# EMG_Interface.net
KiCad netlist of a schematic drawn in Altium Designer
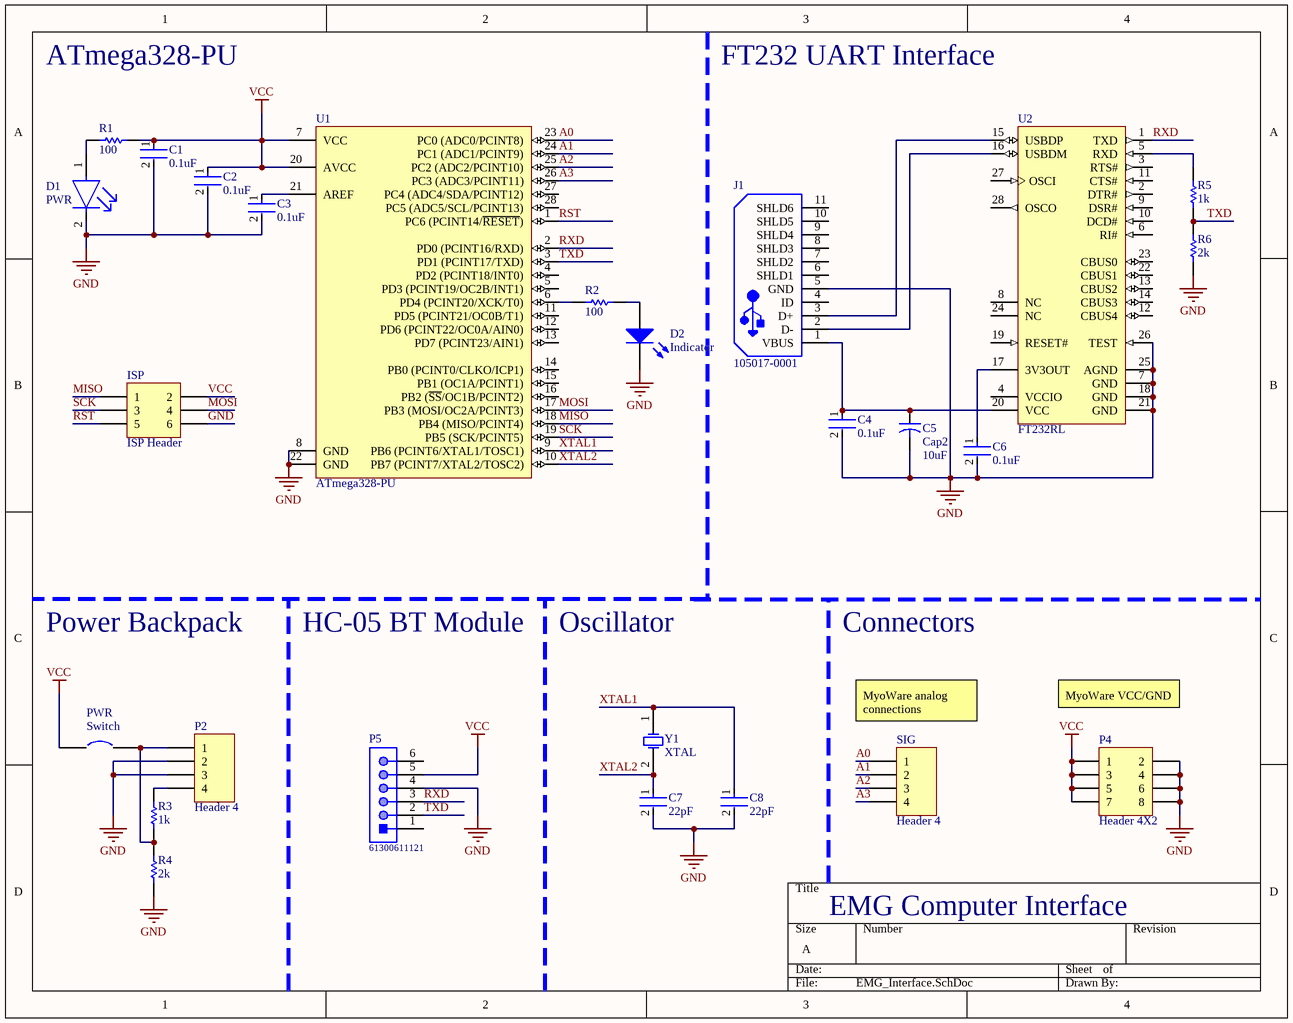
[diagram p0: EMG_Interface.SchDoc]

(export (version "E")
  (design (tool "Eeschema 10.0.6"))
  (components
    (comp (ref "C1")
      (value "0.1uF")
      (footprint "FP-1206-L_3_2_0_2-W_1_6_0-IPC_C")
      (description "General Purpose Ceramic Capacitor, 1206, 100nF, 5%, X7R, 15%, 100V")
      (fields (field (name "TOLERANCE") "5%") (field (name "VOLTAGE") "100V"))
      (libsource (lib "Altium Content Vault") (part "b4654b650e69147ec39a6b967a45e02"))
    )
    (comp (ref "C2")
      (value "0.1uF")
      (footprint "FP-1206-L_3_2_0_2-W_1_6_0-IPC_C")
      (description "General Purpose Ceramic Capacitor, 1206, 100nF, 5%, X7R, 15%, 100V")
      (fields (field (name "TOLERANCE") "5%") (field (name "VOLTAGE") "100V"))
      (libsource (lib "Altium Content Vault") (part "b4654b650e69147ec39a6b967a45e02"))
    )
    (comp (ref "C3")
      (value "0.1uF")
      (footprint "FP-1206-L_3_2_0_2-W_1_6_0-IPC_C")
      (description "General Purpose Ceramic Capacitor, 1206, 100nF, 5%, X7R, 15%, 100V")
      (fields (field (name "TOLERANCE") "5%") (field (name "VOLTAGE") "100V"))
      (libsource (lib "Altium Content Vault") (part "b4654b650e69147ec39a6b967a45e02"))
    )
    (comp (ref "C4")
      (value "0.1uF")
      (footprint "FP-1206-L_3_2_0_2-W_1_6_0-IPC_C")
      (description "General Purpose Ceramic Capacitor, 1206, 100nF, 5%, X7R, 15%, 100V")
      (fields (field (name "TOLERANCE") "5%") (field (name "VOLTAGE") "100V"))
      (libsource (lib "Altium Content Vault") (part "b4654b650e69147ec39a6b967a45e02"))
    )
    (comp (ref "C5")
      (value "Cap2")
      (footprint "CAPR5-4X5")
      (description "Capacitor")
      (fields (field (name "ALTIUM_VALUE") "10uF") (field (name "PUBLISHER") "Altium Limited"))
      (libsource (lib "Miscellaneous Devices") (part "Cap2"))
    )
    (comp (ref "C6")
      (value "0.1uF")
      (footprint "FP-1206-L_3_2_0_2-W_1_6_0-IPC_C")
      (description "General Purpose Ceramic Capacitor, 1206, 100nF, 5%, X7R, 15%, 100V")
      (fields (field (name "TOLERANCE") "5%") (field (name "VOLTAGE") "100V"))
      (libsource (lib "Altium Content Vault") (part "b4654b650e69147ec39a6b967a45e02"))
    )
    (comp (ref "C7")
      (value "22pF")
      (footprint "FP-C1206C-EB-MFG")
      (description "1206 22pF Ceramic Multilayer Capacitor; 50VDC; 125degC; C0G Dielec; +/-5% SMD")
      (fields
        (field (name "OCTOPART") "https://octopart.com/c1206c220j5gactu-kemet-131912")
        (field (name "TOLERANCE") "0.05")
      )
      (libsource (lib "Altium Content Vault") (part "b4654b650e69147ec39a6b967a45e02"))
    )
    (comp (ref "C8")
      (value "22pF")
      (footprint "FP-C1206C-EB-MFG")
      (description "1206 22pF Ceramic Multilayer Capacitor; 50VDC; 125degC; C0G Dielec; +/-5% SMD")
      (fields
        (field (name "OCTOPART") "https://octopart.com/c1206c220j5gactu-kemet-131912")
        (field (name "TOLERANCE") "0.05")
      )
      (libsource (lib "Altium Content Vault") (part "b4654b650e69147ec39a6b967a45e02"))
    )
    (comp (ref "D1")
      (value "PWR")
      (footprint "FP-SML-LX1206GC-TR-MFG")
      (description "LED GREEN CLEAR 1206 SMD")
      (libsource (lib "Altium Content Vault") (part "ab1c01a81903e929fc6c44469aada92"))
    )
    (comp (ref "D2")
      (value "Indicator")
      (footprint "1206_A")
      (description "SMD mono-color Chip LED, WL-SMCW, Super Red")
      (fields (field (name "MANUFACTURER") "Wuerth Elektronik") (field (name "PARTNUMBER") "150120SS75000"))
      (libsource (lib "Altium Content Vault") (part "WE-LED_K1A2-2"))
    )
    (comp (ref "ISP")
      (value "ISP Header")
      (footprint "HDR2X3")
      (description "Header, 3-Pin, Dual row")
      (fields (field (name "PUBLISHER") "Altium Limited"))
      (libsource (lib "Miscellaneous Connectors") (part "Header 3X2"))
    )
    (comp (ref "J1")
      (value "105017-0001")
      (footprint "USB-MICRO-B_V")
      (fields (field (name "MANUFACTURER") "Molex"))
      (libsource (lib "Altium Content Vault") (part "USB-5-6SHLD"))
    )
    (comp (ref "P2")
      (value "Header 4")
      (footprint "HDR1X4")
      (description "Header, 4-Pin")
      (fields (field (name "PUBLISHER") "Altium Limited"))
      (libsource (lib "Miscellaneous Connectors") (part "Header 4"))
    )
    (comp (ref "P4")
      (value "Header 4X2")
      (footprint "HDR2X4")
      (description "Header, 4-Pin, Dual row")
      (fields (field (name "PUBLISHER") "Altium Limited"))
      (libsource (lib "Miscellaneous Connectors") (part "Header 4X2"))
    )
    (comp (ref "P5")
      (value "61300611121")
      (footprint "61300611121")
      (description "THT Vertical Pin Header WR-PHD, Pitch 2.54 mm, Single Row, 6 pins")
      (fields (field (name "MANUFACTURER") "Wurth Elektronik") (field (name "PUBLISHER") "WurthElektronik"))
      (libsource (lib "Altium Content Vault") (part "WE-CN-1P-M-R6"))
    )
    (comp (ref "PWR")
      (value "Switch")
      (footprint "SPST-2")
      (description "Circuit Breaker")
      (fields (field (name "PUBLISHER") "Altium Limited"))
      (libsource (lib "Miscellaneous Devices") (part "Circuit Breaker"))
    )
    (comp (ref "R1")
      (value "100")
      (footprint "RESC3216X70X50LL05T20")
      (fields (field (name "PART NUMBER") "ERJ-P08J101V") (field (name "MANUFACTURER") "Panasonic"))
      (libsource (lib "Altium Content Vault") (part "RES"))
    )
    (comp (ref "R2")
      (value "100")
      (footprint "RESC3216X70X50LL05T20")
      (fields (field (name "PART NUMBER") "ERJ-P08J101V") (field (name "MANUFACTURER") "Panasonic"))
      (libsource (lib "Altium Content Vault") (part "RES"))
    )
    (comp (ref "R3")
      (value "1k")
      (footprint "RESC3216X70X50LL05T20")
      (fields (field (name "MANUFACTURER") "Panasonic") (field (name "PART NUMBER") "ERJ-8ENF1001V"))
      (libsource (lib "Altium Content Vault") (part "RES"))
    )
    (comp (ref "R4")
      (value "2k")
      (footprint "RESC3216X70X50NL05T20")
      (fields (field (name "PART NUMBER") "ERJ-8ENF2001V") (field (name "MANUFACTURER") "Panasonic"))
      (libsource (lib "Altium Content Vault") (part "RES"))
    )
    (comp (ref "R5")
      (value "1k")
      (footprint "RESC3216X70X50LL05T20")
      (fields (field (name "MANUFACTURER") "Panasonic") (field (name "PART NUMBER") "ERJ-8ENF1001V"))
      (libsource (lib "Altium Content Vault") (part "RES"))
    )
    (comp (ref "R6")
      (value "2k")
      (footprint "RESC3216X70X50NL05T20")
      (fields (field (name "PART NUMBER") "ERJ-8ENF2001V") (field (name "MANUFACTURER") "Panasonic"))
      (libsource (lib "Altium Content Vault") (part "RES"))
    )
    (comp (ref "SIG")
      (value "Header 4")
      (footprint "HDR1X4")
      (description "Header, 4-Pin")
      (fields (field (name "PUBLISHER") "Altium Limited"))
      (libsource (lib "Miscellaneous Connectors") (part "Header 4"))
    )
    (comp (ref "U1")
      (value "ATmega328-PU")
      (footprint "28P3")
      (libsource (lib "Altium Content Vault") (part "MC-8B-ATM48-IL28"))
    )
    (comp (ref "U2")
      (value "FT232RL")
      (footprint "FTDI-SSOP-28_M")
      (description "IC USB FS SERIAL UART 28-SSOP")
      (fields (field (name "MANUFACTURER") "FTDI"))
      (libsource (lib "Altium Content Vault") (part "FTDI-FT232-SSOP-28"))
    )
    (comp (ref "Y1")
      (value "XTAL")
      (footprint "R38")
      (description "Crystal Oscillator")
      (fields (field (name "PUBLISHER") "Altium Limited"))
      (libsource (lib "Miscellaneous Devices") (part "XTAL"))
    )
  )
  (nets
    (net (code "1") (name "/A0") (class "Default")
      (node (ref "SIG") (pin "1") (pinfunction "1_1") (pintype "passive"))
      (node (ref "U1") (pin "23") (pinfunction "PC0_(ADC0/PCINT8)_23") (pintype "bidirectional"))
    )
    (net (code "2") (name "/A1") (class "Default")
      (node (ref "SIG") (pin "2") (pinfunction "2_2") (pintype "passive"))
      (node (ref "U1") (pin "24") (pinfunction "PC1_(ADC1/PCINT9)_24") (pintype "bidirectional"))
    )
    (net (code "3") (name "/A2") (class "Default")
      (node (ref "SIG") (pin "3") (pinfunction "3_3") (pintype "passive"))
      (node (ref "U1") (pin "25") (pinfunction "PC2_(ADC2/PCINT10)_25") (pintype "bidirectional"))
    )
    (net (code "4") (name "/A3") (class "Default")
      (node (ref "SIG") (pin "4") (pinfunction "4_4") (pintype "passive"))
      (node (ref "U1") (pin "26") (pinfunction "PC3_(ADC3/PCINT11)_26") (pintype "bidirectional"))
    )
    (net (code "5") (name "/MISO") (class "Default")
      (node (ref "ISP") (pin "1") (pinfunction "1_1") (pintype "passive"))
      (node (ref "U1") (pin "18") (pinfunction "PB4_(MISO/PCINT4)_18") (pintype "bidirectional"))
    )
    (net (code "6") (name "/MOSI") (class "Default")
      (node (ref "ISP") (pin "4") (pinfunction "4_4") (pintype "passive"))
      (node (ref "U1") (pin "17") (pinfunction "PB3_(MOSI/OC2A/PCINT3)_17") (pintype "bidirectional"))
    )
    (net (code "7") (name "/RST") (class "Default")
      (node (ref "ISP") (pin "5") (pinfunction "5_5") (pintype "passive"))
      (node (ref "U1") (pin "1") (pinfunction "PC6_(PCINT14/~{RESET})_1") (pintype "bidirectional"))
    )
    (net (code "8") (name "/RXD") (class "Default")
      (node (ref "P5") (pin "3") (pinfunction "3_3") (pintype "passive"))
      (node (ref "U1") (pin "2") (pinfunction "PD0_(PCINT16/RXD)_2") (pintype "bidirectional"))
      (node (ref "U2") (pin "1") (pinfunction "TXD_1") (pintype "output"))
    )
    (net (code "9") (name "/SCK") (class "Default")
      (node (ref "ISP") (pin "3") (pinfunction "3_3") (pintype "passive"))
      (node (ref "U1") (pin "19") (pinfunction "PB5_(SCK/PCINT5)_19") (pintype "bidirectional"))
    )
    (net (code "10") (name "/TXD") (class "Default")
      (node (ref "P5") (pin "2") (pinfunction "2_2") (pintype "passive"))
      (node (ref "R5") (pin "1") (pinfunction "1_1") (pintype "passive"))
      (node (ref "R6") (pin "2") (pinfunction "2_2") (pintype "passive"))
      (node (ref "U1") (pin "3") (pinfunction "PD1_(PCINT17/TXD)_3") (pintype "bidirectional"))
    )
    (net (code "11") (name "/XTAL1") (class "Default")
      (node (ref "C8") (pin "1") (pinfunction "1_1") (pintype "passive"))
      (node (ref "U1") (pin "9") (pinfunction "PB6_(PCINT6/XTAL1/TOSC1)_9") (pintype "bidirectional"))
      (node (ref "Y1") (pin "1") (pinfunction "OSC1_1") (pintype "passive"))
    )
    (net (code "12") (name "/XTAL2") (class "Default")
      (node (ref "C7") (pin "1") (pinfunction "1_1") (pintype "passive"))
      (node (ref "U1") (pin "10") (pinfunction "PB7_(PCINT7/XTAL2/TOSC2)_10") (pintype "bidirectional"))
      (node (ref "Y1") (pin "2") (pinfunction "OSC2_2") (pintype "passive"))
    )
    (net (code "13") (name "GND") (class "Default")
      (node (ref "C1") (pin "2") (pinfunction "2_2") (pintype "passive"))
      (node (ref "C2") (pin "2") (pinfunction "2_2") (pintype "passive"))
      (node (ref "C3") (pin "2") (pinfunction "2_2") (pintype "passive"))
      (node (ref "C4") (pin "2") (pinfunction "2_2") (pintype "passive"))
      (node (ref "C5") (pin "2") (pinfunction "2_2") (pintype "passive"))
      (node (ref "C6") (pin "2") (pinfunction "2_2") (pintype "passive"))
      (node (ref "C7") (pin "2") (pinfunction "2_2") (pintype "passive"))
      (node (ref "C8") (pin "2") (pinfunction "2_2") (pintype "passive"))
      (node (ref "D1") (pin "2") (pinfunction "C_2") (pintype "passive"))
      (node (ref "D2") (pin "1") (pinfunction "K_1") (pintype "passive"))
      (node (ref "ISP") (pin "6") (pinfunction "6_6") (pintype "passive"))
      (node (ref "J1") (pin "5") (pinfunction "GND_5") (pintype "passive"))
      (node (ref "P2") (pin "2") (pinfunction "2_2") (pintype "passive"))
      (node (ref "P2") (pin "3") (pinfunction "3_3") (pintype "passive"))
      (node (ref "P4") (pin "2") (pinfunction "2_2") (pintype "passive"))
      (node (ref "P4") (pin "4") (pinfunction "4_4") (pintype "passive"))
      (node (ref "P4") (pin "6") (pinfunction "6_6") (pintype "passive"))
      (node (ref "P4") (pin "8") (pinfunction "8_8") (pintype "passive"))
      (node (ref "P5") (pin "4") (pinfunction "4_4") (pintype "passive"))
      (node (ref "R4") (pin "1") (pinfunction "1_1") (pintype "passive"))
      (node (ref "R6") (pin "1") (pinfunction "1_1") (pintype "passive"))
      (node (ref "U1") (pin "22") (pinfunction "GND_22") (pintype "power_in"))
      (node (ref "U1") (pin "8") (pinfunction "GND_8") (pintype "power_in"))
      (node (ref "U2") (pin "18") (pinfunction "GND_18") (pintype "power_in"))
      (node (ref "U2") (pin "21") (pinfunction "GND_21") (pintype "power_in"))
      (node (ref "U2") (pin "25") (pinfunction "AGND_25") (pintype "power_in"))
      (node (ref "U2") (pin "26") (pinfunction "TEST_26") (pintype "input"))
      (node (ref "U2") (pin "7") (pinfunction "GND_7") (pintype "power_in"))
    )
    (net (code "14") (name "Net-(D1-A)") (class "Default")
      (node (ref "D1") (pin "1") (pinfunction "A_1") (pintype "passive"))
      (node (ref "R1") (pin "1") (pinfunction "1_1") (pintype "passive"))
    )
    (net (code "15") (name "Net-(D2-A)") (class "Default")
      (node (ref "D2") (pin "2") (pinfunction "A_2") (pintype "passive"))
      (node (ref "R2") (pin "2") (pinfunction "2_2") (pintype "passive"))
    )
    (net (code "16") (name "Net-(J1-D+)") (class "Default")
      (node (ref "J1") (pin "3") (pinfunction "D+_3") (pintype "passive"))
      (node (ref "U2") (pin "15") (pinfunction "USBDP_15") (pintype "bidirectional"))
    )
    (net (code "17") (name "Net-(J1-D-)") (class "Default")
      (node (ref "J1") (pin "2") (pinfunction "D-_2") (pintype "passive"))
      (node (ref "U2") (pin "16") (pinfunction "USBDM_16") (pintype "bidirectional"))
    )
    (net (code "18") (name "Net-(J1-VBUS)") (class "Default")
      (node (ref "C4") (pin "1") (pinfunction "1_1") (pintype "passive"))
      (node (ref "C5") (pin "1") (pinfunction "1_1") (pintype "passive"))
      (node (ref "J1") (pin "1") (pinfunction "VBUS_1") (pintype "passive"))
      (node (ref "U2") (pin "20") (pinfunction "VCC_20") (pintype "power_in"))
    )
    (net (code "19") (name "Net-(P2-Pad1)") (class "Default")
      (node (ref "P2") (pin "1") (pinfunction "1_1") (pintype "passive"))
      (node (ref "PWR") (pin "2") (pinfunction "2_2") (pintype "passive"))
      (node (ref "R3") (pin "1") (pinfunction "1_1") (pintype "passive"))
      (node (ref "R4") (pin "2") (pinfunction "2_2") (pintype "passive"))
    )
    (net (code "20") (name "Net-(P2-Pad4)") (class "Default")
      (node (ref "P2") (pin "4") (pinfunction "4_4") (pintype "passive"))
      (node (ref "R3") (pin "2") (pinfunction "2_2") (pintype "passive"))
    )
    (net (code "21") (name "Net-(U1-AREF)") (class "Default")
      (node (ref "C3") (pin "1") (pinfunction "1_1") (pintype "passive"))
      (node (ref "U1") (pin "21") (pinfunction "AREF_21") (pintype "power_in"))
    )
    (net (code "22") (name "Net-(U1-PD4_(PCINT20{slash}XCK{slash}T0))") (class "Default")
      (node (ref "R2") (pin "1") (pinfunction "1_1") (pintype "passive"))
      (node (ref "U1") (pin "6") (pinfunction "PD4_(PCINT20/XCK/T0)_6") (pintype "bidirectional"))
    )
    (net (code "23") (name "Net-(U2-3V3OUT)") (class "Default")
      (node (ref "C6") (pin "1") (pinfunction "1_1") (pintype "passive"))
      (node (ref "U2") (pin "17") (pinfunction "3V3OUT_17") (pintype "power_in"))
    )
    (net (code "24") (name "Net-(U2-RXD)") (class "Default")
      (node (ref "R5") (pin "2") (pinfunction "2_2") (pintype "passive"))
      (node (ref "U2") (pin "5") (pinfunction "RXD_5") (pintype "input"))
    )
    (net (code "25") (name "VCC") (class "Default")
      (node (ref "C1") (pin "1") (pinfunction "1_1") (pintype "passive"))
      (node (ref "C2") (pin "1") (pinfunction "1_1") (pintype "passive"))
      (node (ref "ISP") (pin "2") (pinfunction "2_2") (pintype "passive"))
      (node (ref "P4") (pin "1") (pinfunction "1_1") (pintype "passive"))
      (node (ref "P4") (pin "3") (pinfunction "3_3") (pintype "passive"))
      (node (ref "P4") (pin "5") (pinfunction "5_5") (pintype "passive"))
      (node (ref "P4") (pin "7") (pinfunction "7_7") (pintype "passive"))
      (node (ref "P5") (pin "5") (pinfunction "5_5") (pintype "passive"))
      (node (ref "PWR") (pin "1") (pinfunction "1_1") (pintype "passive"))
      (node (ref "R1") (pin "2") (pinfunction "2_2") (pintype "passive"))
      (node (ref "U1") (pin "20") (pinfunction "AVCC_20") (pintype "power_in"))
      (node (ref "U1") (pin "7") (pinfunction "VCC_7") (pintype "power_in"))
    )
    (net (code "26") (name "unconnected-(J1-ID-Pad4)") (class "Default")
      (node (ref "J1") (pin "4") (pinfunction "ID_4") (pintype "passive"))
    )
    (net (code "27") (name "unconnected-(J1-SHLD1-Pad6)") (class "Default")
      (node (ref "J1") (pin "6") (pinfunction "SHLD1_6") (pintype "passive"))
    )
    (net (code "28") (name "unconnected-(J1-SHLD2-Pad7)") (class "Default")
      (node (ref "J1") (pin "7") (pinfunction "SHLD2_7") (pintype "passive"))
    )
    (net (code "29") (name "unconnected-(J1-SHLD3-Pad8)") (class "Default")
      (node (ref "J1") (pin "8") (pinfunction "SHLD3_8") (pintype "passive"))
    )
    (net (code "30") (name "unconnected-(J1-SHLD4-Pad9)") (class "Default")
      (node (ref "J1") (pin "9") (pinfunction "SHLD4_9") (pintype "passive"))
    )
    (net (code "31") (name "unconnected-(J1-SHLD5-Pad10)") (class "Default")
      (node (ref "J1") (pin "10") (pinfunction "SHLD5_10") (pintype "passive"))
    )
    (net (code "32") (name "unconnected-(J1-SHLD6-Pad11)") (class "Default")
      (node (ref "J1") (pin "11") (pinfunction "SHLD6_11") (pintype "passive"))
    )
    (net (code "33") (name "unconnected-(P5-Pad1)") (class "Default")
      (node (ref "P5") (pin "1") (pinfunction "1_1") (pintype "passive"))
    )
    (net (code "34") (name "unconnected-(P5-Pad6)") (class "Default")
      (node (ref "P5") (pin "6") (pinfunction "6_6") (pintype "passive"))
    )
    (net (code "35") (name "unconnected-(U1-PB0_(PCINT0{slash}CLKO{slash}ICP1)-Pad14)") (class "Default")
      (node (ref "U1") (pin "14") (pinfunction "PB0_(PCINT0/CLKO/ICP1)_14") (pintype "bidirectional"))
    )
    (net (code "36") (name "unconnected-(U1-PB1_(OC1A{slash}PCINT1)-Pad15)") (class "Default")
      (node (ref "U1") (pin "15") (pinfunction "PB1_(OC1A/PCINT1)_15") (pintype "bidirectional"))
    )
    (net (code "37") (name "unconnected-(U1-PB2_(~{SS}{slash}OC1B{slash}PCINT2)-Pad16)") (class "Default")
      (node (ref "U1") (pin "16") (pinfunction "PB2_(~{SS}/OC1B/PCINT2)_16") (pintype "bidirectional"))
    )
    (net (code "38") (name "unconnected-(U1-PC4_(ADC4{slash}SDA{slash}PCINT12)-Pad27)") (class "Default")
      (node (ref "U1") (pin "27") (pinfunction "PC4_(ADC4/SDA/PCINT12)_27") (pintype "bidirectional"))
    )
    (net (code "39") (name "unconnected-(U1-PC5_(ADC5{slash}SCL{slash}PCINT13)-Pad28)") (class "Default")
      (node (ref "U1") (pin "28") (pinfunction "PC5_(ADC5/SCL/PCINT13)_28") (pintype "bidirectional"))
    )
    (net (code "40") (name "unconnected-(U1-PD2_(PCINT18{slash}INT0)-Pad4)") (class "Default")
      (node (ref "U1") (pin "4") (pinfunction "PD2_(PCINT18/INT0)_4") (pintype "bidirectional"))
    )
    (net (code "41") (name "unconnected-(U1-PD3_(PCINT19{slash}OC2B{slash}INT1)-Pad5)") (class "Default")
      (node (ref "U1") (pin "5") (pinfunction "PD3_(PCINT19/OC2B/INT1)_5") (pintype "bidirectional"))
    )
    (net (code "42") (name "unconnected-(U1-PD5_(PCINT21{slash}OC0B{slash}T1)-Pad11)") (class "Default")
      (node (ref "U1") (pin "11") (pinfunction "PD5_(PCINT21/OC0B/T1)_11") (pintype "bidirectional"))
    )
    (net (code "43") (name "unconnected-(U1-PD6_(PCINT22{slash}OC0A{slash}AIN0)-Pad12)") (class "Default")
      (node (ref "U1") (pin "12") (pinfunction "PD6_(PCINT22/OC0A/AIN0)_12") (pintype "bidirectional"))
    )
    (net (code "44") (name "unconnected-(U1-PD7_(PCINT23{slash}AIN1)-Pad13)") (class "Default")
      (node (ref "U1") (pin "13") (pinfunction "PD7_(PCINT23/AIN1)_13") (pintype "bidirectional"))
    )
    (net (code "45") (name "unconnected-(U2-CBUS0-Pad23)") (class "Default")
      (node (ref "U2") (pin "23") (pinfunction "CBUS0_23") (pintype "bidirectional"))
    )
    (net (code "46") (name "unconnected-(U2-CBUS1-Pad22)") (class "Default")
      (node (ref "U2") (pin "22") (pinfunction "CBUS1_22") (pintype "bidirectional"))
    )
    (net (code "47") (name "unconnected-(U2-CBUS2-Pad13)") (class "Default")
      (node (ref "U2") (pin "13") (pinfunction "CBUS2_13") (pintype "bidirectional"))
    )
    (net (code "48") (name "unconnected-(U2-CBUS3-Pad14)") (class "Default")
      (node (ref "U2") (pin "14") (pinfunction "CBUS3_14") (pintype "bidirectional"))
    )
    (net (code "49") (name "unconnected-(U2-CBUS4-Pad12)") (class "Default")
      (node (ref "U2") (pin "12") (pinfunction "CBUS4_12") (pintype "bidirectional"))
    )
    (net (code "50") (name "unconnected-(U2-CTS#-Pad11)") (class "Default")
      (node (ref "U2") (pin "11") (pinfunction "CTS#_11") (pintype "input"))
    )
    (net (code "51") (name "unconnected-(U2-DCD#-Pad10)") (class "Default")
      (node (ref "U2") (pin "10") (pinfunction "DCD#_10") (pintype "input"))
    )
    (net (code "52") (name "unconnected-(U2-DSR#-Pad9)") (class "Default")
      (node (ref "U2") (pin "9") (pinfunction "DSR#_9") (pintype "input"))
    )
    (net (code "53") (name "unconnected-(U2-DTR#-Pad2)") (class "Default")
      (node (ref "U2") (pin "2") (pinfunction "DTR#_2") (pintype "output"))
    )
    (net (code "54") (name "unconnected-(U2-NC-Pad8)") (class "Default")
      (node (ref "U2") (pin "8") (pinfunction "NC_8") (pintype "passive"))
    )
    (net (code "55") (name "unconnected-(U2-NC-Pad24)") (class "Default")
      (node (ref "U2") (pin "24") (pinfunction "NC_24") (pintype "passive"))
    )
    (net (code "56") (name "unconnected-(U2-OSCI-Pad27)") (class "Default")
      (node (ref "U2") (pin "27") (pinfunction "OSCI_27") (pintype "input"))
    )
    (net (code "57") (name "unconnected-(U2-OSCO-Pad28)") (class "Default")
      (node (ref "U2") (pin "28") (pinfunction "OSCO_28") (pintype "output"))
    )
    (net (code "58") (name "unconnected-(U2-RESET#-Pad19)") (class "Default")
      (node (ref "U2") (pin "19") (pinfunction "RESET#_19") (pintype "input"))
    )
    (net (code "59") (name "unconnected-(U2-RI#-Pad6)") (class "Default")
      (node (ref "U2") (pin "6") (pinfunction "RI#_6") (pintype "input"))
    )
    (net (code "60") (name "unconnected-(U2-RTS#-Pad3)") (class "Default")
      (node (ref "U2") (pin "3") (pinfunction "RTS#_3") (pintype "output"))
    )
    (net (code "61") (name "unconnected-(U2-VCCIO-Pad4)") (class "Default")
      (node (ref "U2") (pin "4") (pinfunction "VCCIO_4") (pintype "power_in"))
    )
  )
)
